# LVDS_repeater.net
KiCad netlist of a schematic drawn in Altium Designer
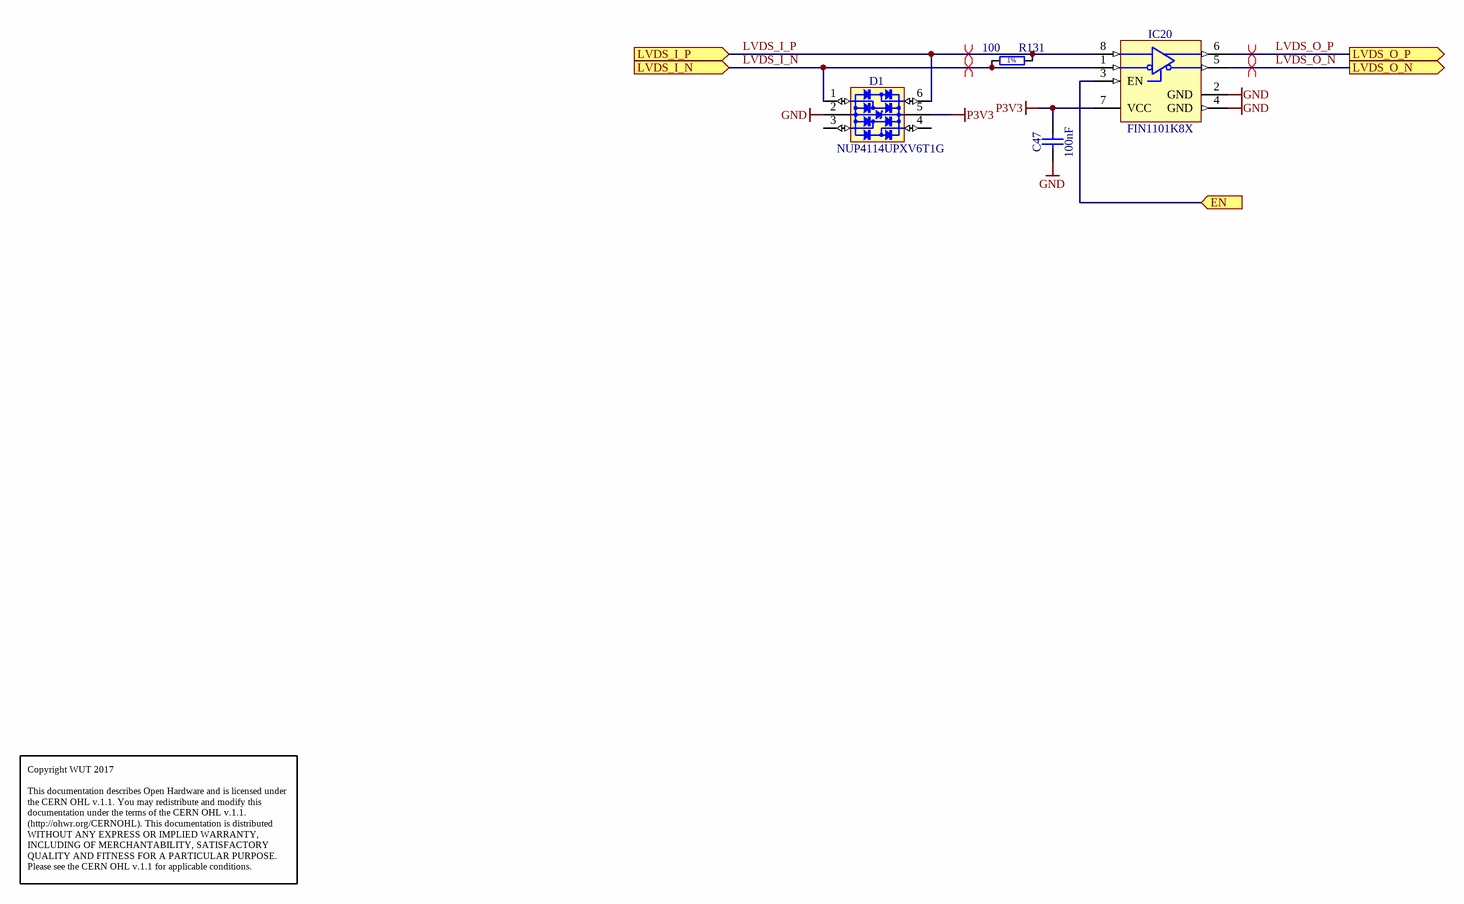
[diagram p0: LVDS_repeater.SchDoc]

(export (version "E")
  (design (tool "Eeschema 10.0.6"))
  (components
    (comp (ref "C47")
      (value "100nF")
      (footprint "CAPC1005X55N")
      (description "Non-polarised capacitor")
      (fields
        (field (name "PART NUMBER") "CC0402_100NF_16V_10%_X5R")
        (field (name "VOLTAGE") "16V")
        (field (name "AUTHOR") "CERN DEM JLC")
      )
      (libsource (lib "Capacitors") (part "Capacitor - non polarized"))
    )
    (comp (ref "D1")
      (value "NUP4114UPXV6T1G")
      (footprint "SOTFL50P160X60-6N")
      (fields
        (field (name "VOLTAGE") "5.5V")
        (field (name "MANUFACTURER") "ON SEMICONDUCTOR")
        (field (name "AUTHOR") "CERN DEM JLC")
      )
      (libsource (lib "ICs And Semiconductors") (part "NUP4114"))
    )
    (comp (ref "IC20")
      (value "FIN1101K8X")
      (footprint "SOP50P310X90-8N")
      (description "LVDS Single Port High Speed Repeater")
      (fields (field (name "MANUFACTURER") "FAIRCHILD SEMICONDUCTOR") (field (name "AUTHOR") "CERN DEM JLC"))
      (libsource (lib "ICs And Semiconductors") (part "FIN1101K8X"))
    )
    (comp (ref "R131")
      (value "100")
      (footprint "RESC1005X40N")
      (description "Resistor - 1%")
      (fields
        (field (name "PART NUMBER") "R0402_100R_1%_0.1W_100PPM")
        (field (name "POWER") "0.1W")
        (field (name "AUTHOR") "CERN DEM JLC")
      )
      (libsource (lib "Resistors") (part "Resistor - 1%"))
    )
  )
  (nets
    (net (code "1") (name "/EN") (class "Default")
      (node (ref "IC20") (pin "3") (pinfunction "EN_3") (pintype "input"))
    )
    (net (code "2") (name "/LVDS_I_N") (class "Default")
      (node (ref "D1") (pin "1") (pinfunction "I/O1_1") (pintype "bidirectional"))
      (node (ref "IC20") (pin "1") (pinfunction "RIN-_1") (pintype "input"))
      (node (ref "R131") (pin "1") (pinfunction "1_1") (pintype "passive"))
    )
    (net (code "3") (name "/LVDS_I_P") (class "Default")
      (node (ref "D1") (pin "6") (pinfunction "I/O4_6") (pintype "bidirectional"))
      (node (ref "IC20") (pin "8") (pinfunction "RIN+_8") (pintype "input"))
      (node (ref "R131") (pin "2") (pinfunction "2_2") (pintype "passive"))
    )
    (net (code "4") (name "/LVDS_O_N") (class "Default")
      (node (ref "IC20") (pin "5") (pinfunction "DOUT-_5") (pintype "output"))
    )
    (net (code "5") (name "/LVDS_O_P") (class "Default")
      (node (ref "IC20") (pin "6") (pinfunction "DOUT+_6") (pintype "output"))
    )
    (net (code "6") (name "GND") (class "Default")
      (node (ref "C47") (pin "1") (pinfunction "1_1") (pintype "passive"))
      (node (ref "D1") (pin "2") (pinfunction "GND_2") (pintype "power_in"))
      (node (ref "IC20") (pin "2") (pinfunction "GND_2") (pintype "power_in"))
      (node (ref "IC20") (pin "4") (pinfunction "GND_4") (pintype "output"))
    )
    (net (code "7") (name "P3V3") (class "Default")
      (node (ref "C47") (pin "2") (pinfunction "2_2") (pintype "passive"))
      (node (ref "D1") (pin "5") (pinfunction "VBUS_5") (pintype "power_in"))
      (node (ref "IC20") (pin "7") (pinfunction "VCC_7") (pintype "power_in"))
    )
    (net (code "8") (name "unconnected-(D1-I{slash}O2-Pad3)") (class "Default")
      (node (ref "D1") (pin "3") (pinfunction "I/O2_3") (pintype "bidirectional"))
    )
    (net (code "9") (name "unconnected-(D1-I{slash}O3-Pad4)") (class "Default")
      (node (ref "D1") (pin "4") (pinfunction "I/O3_4") (pintype "bidirectional"))
    )
  )
)
